# laserDriver.net
KiCad netlist of a schematic drawn in EAGLE
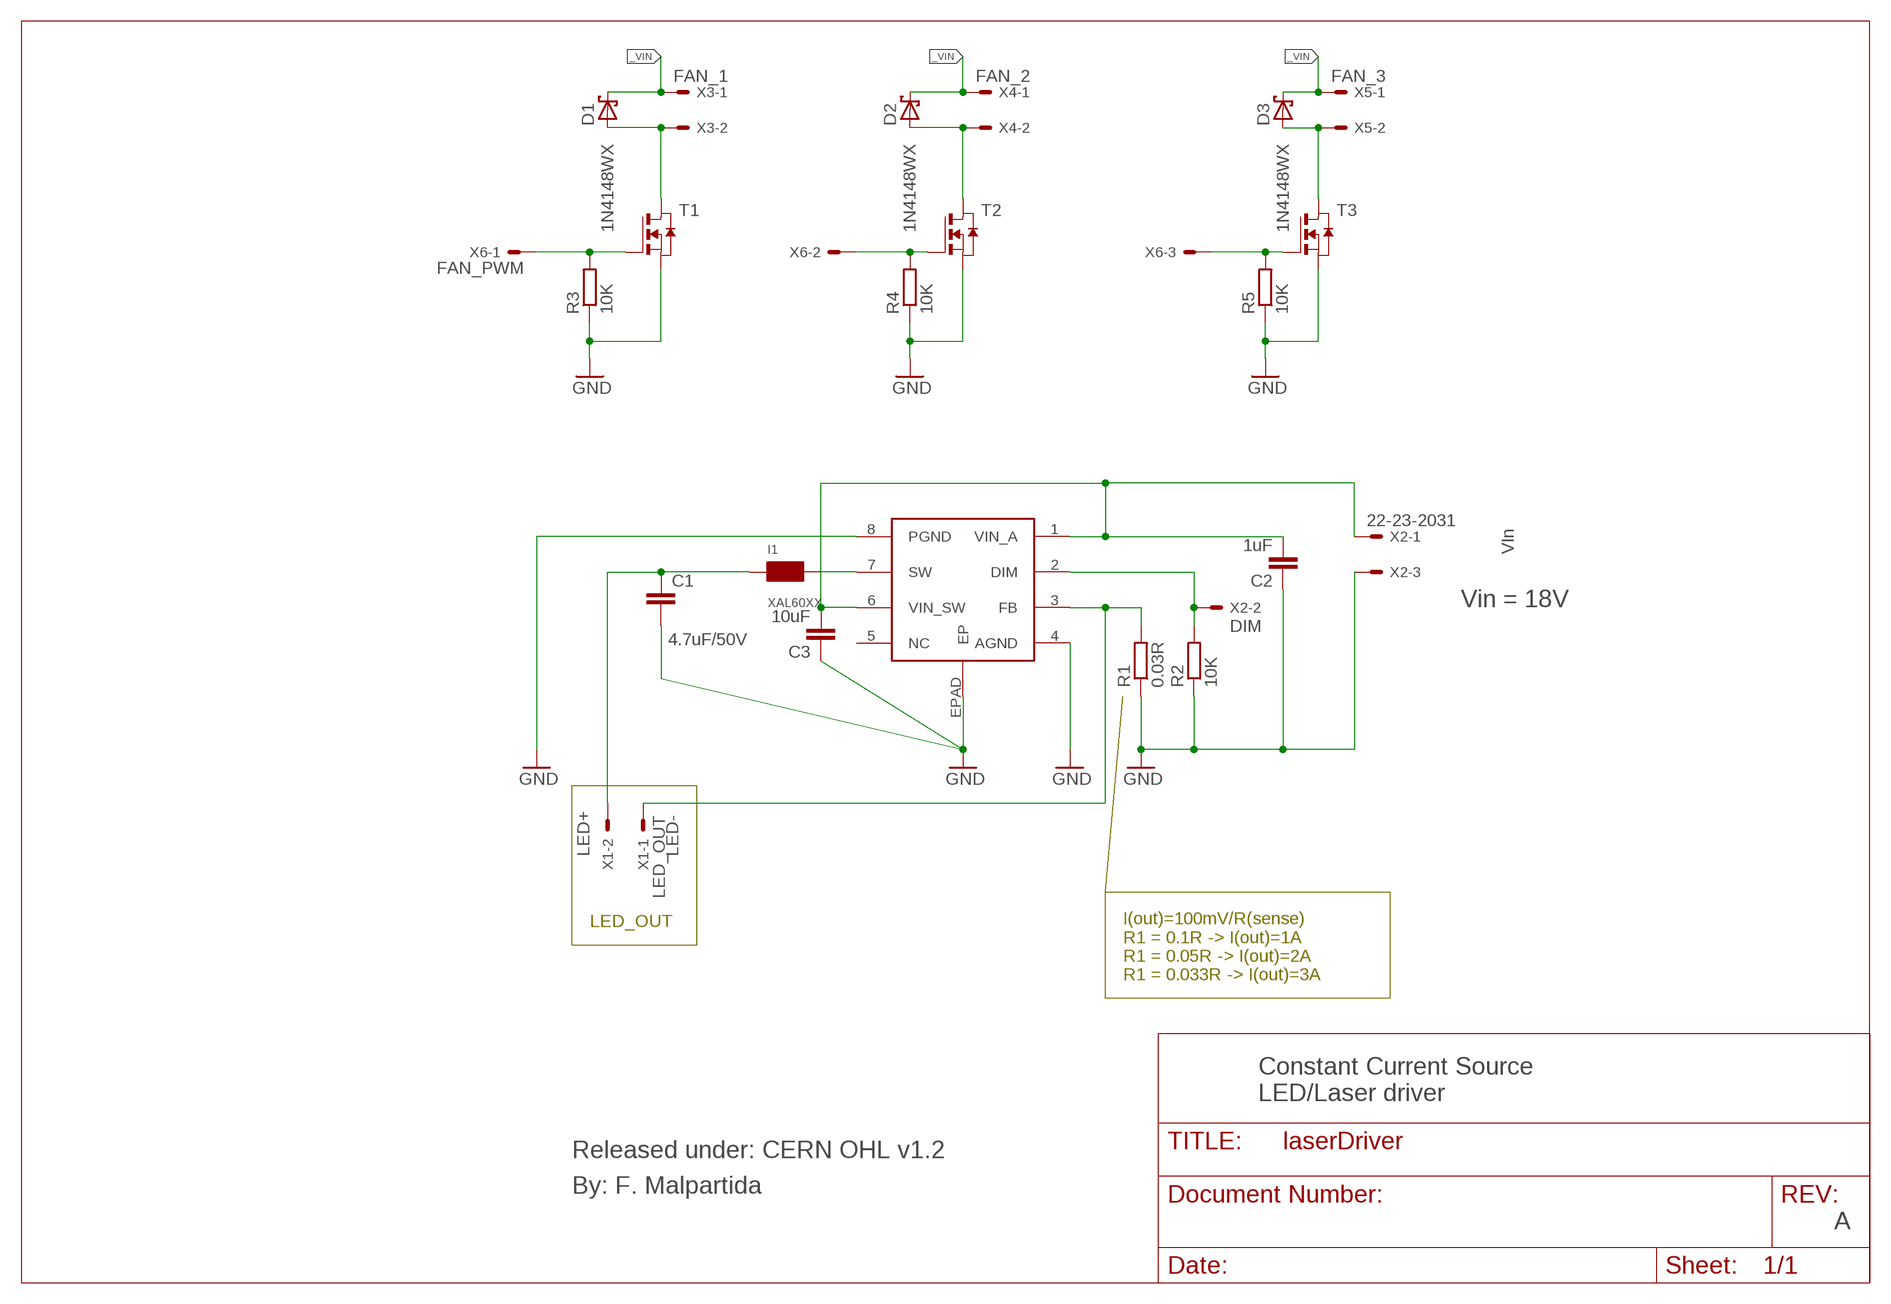
[diagram p0: schematic, sheet 1]

(export (version "E")
  (design (tool "Eeschema 10.0.6"))
  (components
    (comp (ref "C1")
      (value "4.7uF/50V")
      (footprint "eagle-import:C1206")
      (libsource (lib "eagle-import") (part "C-EUC1206"))
    )
    (comp (ref "C2")
      (value "1uF")
      (footprint "eagle-import:C1206")
      (libsource (lib "eagle-import") (part "C-EUC1206"))
    )
    (comp (ref "C3")
      (value "10uF")
      (footprint "eagle-import:C1206")
      (libsource (lib "eagle-import") (part "C-EUC1206"))
    )
    (comp (ref "D1")
      (value "1N4148WX")
      (footprint "eagle-import:SOD323_ST")
      (libsource (lib "eagle-import") (part "BAT60J"))
    )
    (comp (ref "D2")
      (value "1N4148WX")
      (footprint "eagle-import:SOD323_ST")
      (libsource (lib "eagle-import") (part "BAT60J"))
    )
    (comp (ref "D3")
      (value "1N4148WX")
      (footprint "eagle-import:SOD323_ST")
      (libsource (lib "eagle-import") (part "BAT60J"))
    )
    (comp (ref "I1")
      (value "XAL60XX")
      (footprint "eagle-import:XAL60XX")
      (libsource (lib "eagle-import") (part "XAL60XX"))
    )
    (comp (ref "R1")
      (value "0.03R")
      (footprint "eagle-import:R2512")
      (libsource (lib "eagle-import") (part "R-EU_R2512"))
    )
    (comp (ref "R2")
      (value "10K")
      (footprint "eagle-import:M0805")
      (libsource (lib "eagle-import") (part "R-EU_M0805"))
    )
    (comp (ref "R3")
      (value "10K")
      (footprint "eagle-import:M0805")
      (libsource (lib "eagle-import") (part "R-EU_M0805"))
    )
    (comp (ref "R4")
      (value "10K")
      (footprint "eagle-import:M0805")
      (libsource (lib "eagle-import") (part "R-EU_M0805"))
    )
    (comp (ref "R5")
      (value "10K")
      (footprint "eagle-import:M0805")
      (libsource (lib "eagle-import") (part "R-EU_M0805"))
    )
    (comp (ref "T1")
      (value "NMOSSOT23")
      (footprint "eagle-import:SOT-23")
      (libsource (lib "eagle-import") (part "NMOSSOT23"))
    )
    (comp (ref "T2")
      (value "NMOSSOT23")
      (footprint "eagle-import:SOT-23")
      (libsource (lib "eagle-import") (part "NMOSSOT23"))
    )
    (comp (ref "T3")
      (value "NMOSSOT23")
      (footprint "eagle-import:SOT-23")
      (libsource (lib "eagle-import") (part "NMOSSOT23"))
    )
    (comp (ref "U1")
      (value "LED2001")
      (footprint "eagle-import:SO08_PWR")
      (libsource (lib "eagle-import") (part "LED2001"))
    )
    (comp (ref "X1")
      (value "LED_OUT")
      (footprint "eagle-import:22-23-2021")
      (fields (field (name "MF") "MOLEX") (field (name "MPN") "22-23-2021"))
      (libsource (lib "eagle-import") (part "22-23-2021"))
    )
    (comp (ref "X2")
      (value "22-23-2031")
      (footprint "eagle-import:22-23-2031")
      (fields (field (name "MF") "MOLEX"))
      (libsource (lib "eagle-import") (part "22-23-2031"))
    )
    (comp (ref "X3")
      (value "FAN_1")
      (footprint "eagle-import:22-23-2021")
      (fields (field (name "MF") "MOLEX") (field (name "MPN") "22-23-2021"))
      (libsource (lib "eagle-import") (part "22-23-2021"))
    )
    (comp (ref "X4")
      (value "FAN_2")
      (footprint "eagle-import:22-23-2021")
      (fields (field (name "MF") "MOLEX") (field (name "MPN") "22-23-2021"))
      (libsource (lib "eagle-import") (part "22-23-2021"))
    )
    (comp (ref "X5")
      (value "FAN_3")
      (footprint "eagle-import:22-23-2021")
      (fields (field (name "MF") "MOLEX") (field (name "MPN") "22-23-2021"))
      (libsource (lib "eagle-import") (part "22-23-2021"))
    )
    (comp (ref "X6")
      (value "FAN_PWM")
      (footprint "eagle-import:22-23-2031")
      (fields (field (name "MF") "MOLEX") (field (name "MPN") "22-23-2031"))
      (libsource (lib "eagle-import") (part "22-23-2031"))
    )
  )
  (nets
    (net (code "1") (name "GND") (class "Default")
      (node (ref "C1") (pin "2") (pinfunction "2_2") (pintype "passive"))
      (node (ref "C2") (pin "1") (pinfunction "1_1") (pintype "passive"))
      (node (ref "C3") (pin "1") (pinfunction "1_1") (pintype "passive"))
      (node (ref "R1") (pin "1") (pinfunction "1_1") (pintype "passive"))
      (node (ref "R2") (pin "1") (pinfunction "1_1") (pintype "passive"))
      (node (ref "R3") (pin "1") (pinfunction "1_1") (pintype "passive"))
      (node (ref "R4") (pin "1") (pinfunction "1_1") (pintype "passive"))
      (node (ref "R5") (pin "1") (pinfunction "1_1") (pintype "passive"))
      (node (ref "T1") (pin "2") (pinfunction "S_2") (pintype "passive"))
      (node (ref "T2") (pin "2") (pinfunction "S_2") (pintype "passive"))
      (node (ref "T3") (pin "2") (pinfunction "S_2") (pintype "passive"))
      (node (ref "U1") (pin "4") (pinfunction "AGND_4") (pintype "bidirectional"))
      (node (ref "U1") (pin "8") (pinfunction "PGND_8") (pintype "bidirectional"))
      (node (ref "U1") (pin "EPAD") (pinfunction "EP_EPAD") (pintype "bidirectional"))
      (node (ref "X2") (pin "3") (pinfunction "S_3") (pintype "passive"))
    )
    (net (code "2") (name "Net-(T1-D)") (class "Default")
      (node (ref "D1") (pin "A") (pinfunction "A_A") (pintype "passive"))
      (node (ref "T1") (pin "1") (pinfunction "D_1") (pintype "passive"))
      (node (ref "X3") (pin "2") (pinfunction "S_2") (pintype "passive"))
    )
    (net (code "3") (name "Net-(T1-G)") (class "Default")
      (node (ref "R3") (pin "2") (pinfunction "2_2") (pintype "passive"))
      (node (ref "T1") (pin "3") (pinfunction "G_3") (pintype "passive"))
      (node (ref "X6") (pin "1") (pinfunction "S_1") (pintype "passive"))
    )
    (net (code "4") (name "Net-(T2-D)") (class "Default")
      (node (ref "D2") (pin "A") (pinfunction "A_A") (pintype "passive"))
      (node (ref "T2") (pin "1") (pinfunction "D_1") (pintype "passive"))
      (node (ref "X4") (pin "2") (pinfunction "S_2") (pintype "passive"))
    )
    (net (code "5") (name "Net-(T2-G)") (class "Default")
      (node (ref "R4") (pin "2") (pinfunction "2_2") (pintype "passive"))
      (node (ref "T2") (pin "3") (pinfunction "G_3") (pintype "passive"))
      (node (ref "X6") (pin "2") (pinfunction "S_2") (pintype "passive"))
    )
    (net (code "6") (name "Net-(T3-D)") (class "Default")
      (node (ref "D3") (pin "A") (pinfunction "A_A") (pintype "passive"))
      (node (ref "T3") (pin "1") (pinfunction "D_1") (pintype "passive"))
      (node (ref "X5") (pin "2") (pinfunction "S_2") (pintype "passive"))
    )
    (net (code "7") (name "Net-(T3-G)") (class "Default")
      (node (ref "R5") (pin "2") (pinfunction "2_2") (pintype "passive"))
      (node (ref "T3") (pin "3") (pinfunction "G_3") (pintype "passive"))
      (node (ref "X6") (pin "3") (pinfunction "S_3") (pintype "passive"))
    )
    (net (code "8") (name "Net-(U1-DIM)") (class "Default")
      (node (ref "R2") (pin "2") (pinfunction "2_2") (pintype "passive"))
      (node (ref "U1") (pin "2") (pinfunction "DIM_2") (pintype "bidirectional"))
      (node (ref "X2") (pin "2") (pinfunction "S_2") (pintype "passive"))
    )
    (net (code "9") (name "Net-(U1-FB)") (class "Default")
      (node (ref "R1") (pin "2") (pinfunction "2_2") (pintype "passive"))
      (node (ref "U1") (pin "3") (pinfunction "FB_3") (pintype "bidirectional"))
      (node (ref "X1") (pin "1") (pinfunction "S_1") (pintype "passive"))
    )
    (net (code "10") (name "Net-(U1-SW)") (class "Default")
      (node (ref "I1") (pin "P$2") (pinfunction "P$2_P$2") (pintype "bidirectional"))
      (node (ref "U1") (pin "7") (pinfunction "SW_7") (pintype "bidirectional"))
    )
    (net (code "11") (name "Net-(X1B-S)") (class "Default")
      (node (ref "C1") (pin "1") (pinfunction "1_1") (pintype "passive"))
      (node (ref "I1") (pin "P$1") (pinfunction "P$1_P$1") (pintype "bidirectional"))
      (node (ref "X1") (pin "2") (pinfunction "S_2") (pintype "passive"))
    )
    (net (code "12") (name "_VIN") (class "Default")
      (node (ref "C2") (pin "2") (pinfunction "2_2") (pintype "passive"))
      (node (ref "C3") (pin "2") (pinfunction "2_2") (pintype "passive"))
      (node (ref "D1") (pin "C") (pinfunction "C_C") (pintype "passive"))
      (node (ref "D2") (pin "C") (pinfunction "C_C") (pintype "passive"))
      (node (ref "D3") (pin "C") (pinfunction "C_C") (pintype "passive"))
      (node (ref "U1") (pin "1") (pinfunction "VIN_A_1") (pintype "bidirectional"))
      (node (ref "U1") (pin "6") (pinfunction "VIN_SW_6") (pintype "bidirectional"))
      (node (ref "X2") (pin "1") (pinfunction "S_1") (pintype "passive"))
      (node (ref "X3") (pin "1") (pinfunction "S_1") (pintype "passive"))
      (node (ref "X4") (pin "1") (pinfunction "S_1") (pintype "passive"))
      (node (ref "X5") (pin "1") (pinfunction "S_1") (pintype "passive"))
    )
    (net (code "13") (name "unconnected-(U1-NC-Pad5)") (class "Default")
      (node (ref "U1") (pin "5") (pinfunction "NC_5") (pintype "bidirectional"))
    )
  )
)
